# ALU.net
KiCad netlist of a schematic drawn in Altium Designer
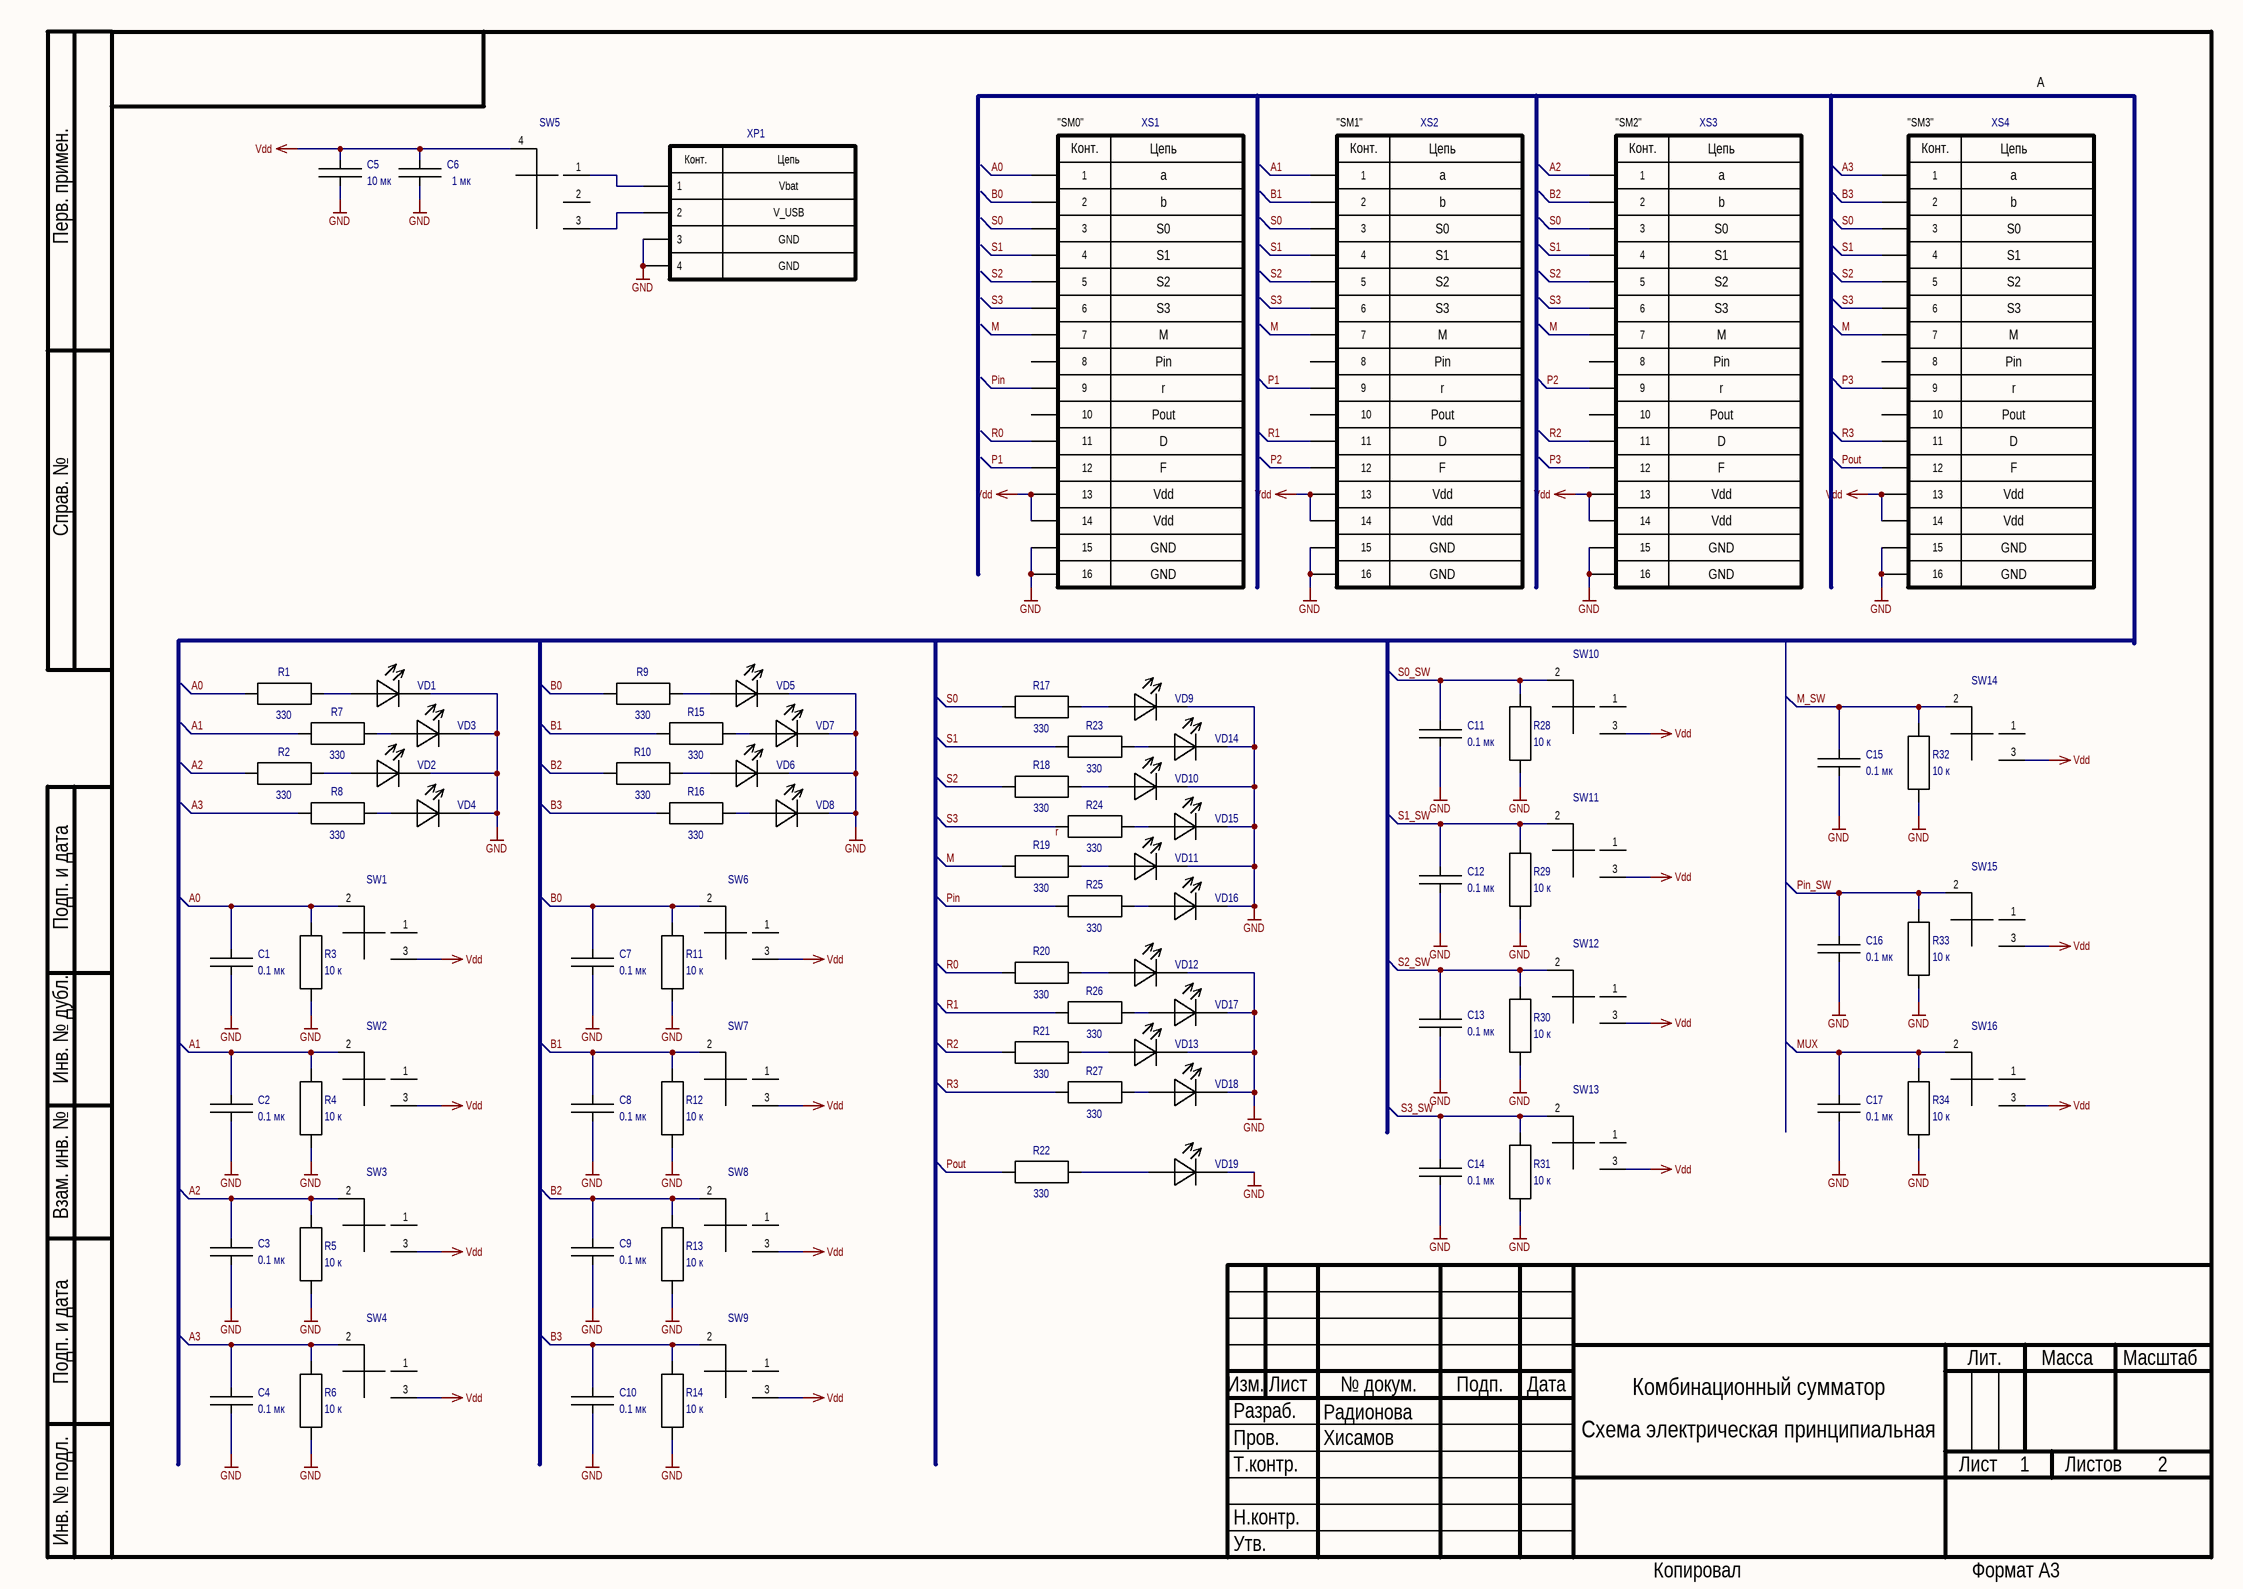
[diagram p0: ALU (4).SchDoc]

(export (version "E")
  (design (tool "Eeschema 10.0.6"))
  (components
    (comp (ref "C1")
      (value "0.1 мк")
      (footprint "platforma:C0603")
      (fields (field (name "Comment") "0.1 мкФ ±* * * *, *"))
      (libsource (lib "Lisaveta") (part "C"))
    )
    (comp (ref "C2")
      (value "0.1 мк")
      (footprint "platforma:C0603")
      (fields (field (name "Comment") "0.1 мкФ ±* * * *, *"))
      (libsource (lib "Lisaveta") (part "C"))
    )
    (comp (ref "C3")
      (value "0.1 мк")
      (footprint "platforma:C0603")
      (fields (field (name "Comment") "0.1 мкФ ±* * * *, *"))
      (libsource (lib "Lisaveta") (part "C"))
    )
    (comp (ref "C4")
      (value "0.1 мк")
      (footprint "platforma:C0603")
      (fields (field (name "Comment") "0.1 мкФ ±* * * *, *"))
      (libsource (lib "Lisaveta") (part "C"))
    )
    (comp (ref "C5")
      (value "10 мк")
      (footprint "platforma:C0603")
      (fields (field (name "Comment") "10 мкФ ±* * * *, *"))
      (libsource (lib "Lisaveta") (part "C"))
    )
    (comp (ref "C6")
      (value "1 мк")
      (footprint "platforma:C0603")
      (fields (field (name "Comment") "1 мкФ ±* * * *, *"))
      (libsource (lib "Lisaveta") (part "C"))
    )
    (comp (ref "C7")
      (value "0.1 мк")
      (footprint "platforma:C0603")
      (fields (field (name "Comment") "0.1 мкФ ±* * * *, *"))
      (libsource (lib "Lisaveta") (part "C"))
    )
    (comp (ref "C8")
      (value "0.1 мк")
      (footprint "platforma:C0603")
      (fields (field (name "Comment") "0.1 мкФ ±* * * *, *"))
      (libsource (lib "Lisaveta") (part "C"))
    )
    (comp (ref "C9")
      (value "0.1 мк")
      (footprint "platforma:C0603")
      (fields (field (name "Comment") "0.1 мкФ ±* * * *, *"))
      (libsource (lib "Lisaveta") (part "C"))
    )
    (comp (ref "C10")
      (value "0.1 мк")
      (footprint "platforma:C0603")
      (fields (field (name "Comment") "0.1 мкФ ±* * * *, *"))
      (libsource (lib "Lisaveta") (part "C"))
    )
    (comp (ref "C11")
      (value "0.1 мк")
      (footprint "platforma:C0603")
      (fields (field (name "Comment") "0.1 мкФ ±* * * *, *"))
      (libsource (lib "Lisaveta") (part "C"))
    )
    (comp (ref "C12")
      (value "0.1 мк")
      (footprint "platforma:C0603")
      (fields (field (name "Comment") "0.1 мкФ ±* * * *, *"))
      (libsource (lib "Lisaveta") (part "C"))
    )
    (comp (ref "C13")
      (value "0.1 мк")
      (footprint "platforma:C0603")
      (fields (field (name "Comment") "0.1 мкФ ±* * * *, *"))
      (libsource (lib "Lisaveta") (part "C"))
    )
    (comp (ref "C14")
      (value "0.1 мк")
      (footprint "platforma:C0603")
      (fields (field (name "Comment") "0.1 мкФ ±* * * *, *"))
      (libsource (lib "Lisaveta") (part "C"))
    )
    (comp (ref "C15")
      (value "0.1 мк")
      (footprint "platforma:C0603")
      (fields (field (name "Comment") "0.1 мкФ ±* * * *, *"))
      (libsource (lib "Lisaveta") (part "C"))
    )
    (comp (ref "C16")
      (value "0.1 мк")
      (footprint "platforma:C0603")
      (fields (field (name "Comment") "0.1 мкФ ±* * * *, *"))
      (libsource (lib "Lisaveta") (part "C"))
    )
    (comp (ref "C17")
      (value "0.1 мк")
      (footprint "platforma:C0603")
      (fields (field (name "Comment") "0.1 мкФ ±* * * *, *"))
      (libsource (lib "Lisaveta") (part "C"))
    )
    (comp (ref "R1")
      (value "330")
      (footprint "ALU:P1-12-0.1(0603)")
      (fields (field (name "Comment") "330Ом ±* *, *"))
      (libsource (lib "ALU") (part "R - Резистор"))
    )
    (comp (ref "R2")
      (value "330")
      (footprint "ALU:P1-12-0.1(0603)")
      (fields (field (name "Comment") "330Ом ±* *, *"))
      (libsource (lib "ALU") (part "R - Резистор"))
    )
    (comp (ref "R3")
      (value "10 к")
      (footprint "P1-12-0.1(0603)")
      (fields (field (name "Comment") "10 кОм ±* *, *"))
      (libsource (lib "Lisaveta") (part "R_1"))
    )
    (comp (ref "R4")
      (value "10 к")
      (footprint "P1-12-0.1(0603)")
      (fields (field (name "Comment") "10 кОм ±* *, *"))
      (libsource (lib "Lisaveta") (part "R_1"))
    )
    (comp (ref "R5")
      (value "10 к")
      (footprint "P1-12-0.1(0603)")
      (fields (field (name "Comment") "10 кОм ±* *, *"))
      (libsource (lib "Lisaveta") (part "R_1"))
    )
    (comp (ref "R6")
      (value "10 к")
      (footprint "P1-12-0.1(0603)")
      (fields (field (name "Comment") "10 кОм ±* *, *"))
      (libsource (lib "Lisaveta") (part "R_1"))
    )
    (comp (ref "R7")
      (value "330")
      (footprint "ALU:P1-12-0.1(0603)")
      (fields (field (name "Comment") "330Ом ±* *, *"))
      (libsource (lib "ALU") (part "R - Резистор"))
    )
    (comp (ref "R8")
      (value "330")
      (footprint "ALU:P1-12-0.1(0603)")
      (fields (field (name "Comment") "330Ом ±* *, *"))
      (libsource (lib "ALU") (part "R - Резистор"))
    )
    (comp (ref "R9")
      (value "330")
      (footprint "ALU:P1-12-0.1(0603)")
      (fields (field (name "Comment") "330Ом ±* *, *"))
      (libsource (lib "ALU") (part "R - Резистор"))
    )
    (comp (ref "R10")
      (value "330")
      (footprint "ALU:P1-12-0.1(0603)")
      (fields (field (name "Comment") "330Ом ±* *, *"))
      (libsource (lib "ALU") (part "R - Резистор"))
    )
    (comp (ref "R11")
      (value "10 к")
      (footprint "P1-12-0.1(0603)")
      (fields (field (name "Comment") "10 кОм ±* *, *"))
      (libsource (lib "Lisaveta") (part "R_1"))
    )
    (comp (ref "R12")
      (value "10 к")
      (footprint "P1-12-0.1(0603)")
      (fields (field (name "Comment") "10 кОм ±* *, *"))
      (libsource (lib "Lisaveta") (part "R_1"))
    )
    (comp (ref "R13")
      (value "10 к")
      (footprint "P1-12-0.1(0603)")
      (fields (field (name "Comment") "10 кОм ±* *, *"))
      (libsource (lib "Lisaveta") (part "R_1"))
    )
    (comp (ref "R14")
      (value "10 к")
      (footprint "P1-12-0.1(0603)")
      (fields (field (name "Comment") "10 кОм ±* *, *"))
      (libsource (lib "Lisaveta") (part "R_1"))
    )
    (comp (ref "R15")
      (value "330")
      (footprint "ALU:P1-12-0.1(0603)")
      (fields (field (name "Comment") "330Ом ±* *, *"))
      (libsource (lib "ALU") (part "R - Резистор"))
    )
    (comp (ref "R16")
      (value "330")
      (footprint "ALU:P1-12-0.1(0603)")
      (fields (field (name "Comment") "330Ом ±* *, *"))
      (libsource (lib "ALU") (part "R - Резистор"))
    )
    (comp (ref "R17")
      (value "330")
      (footprint "ALU:P1-12-0.1(0603)")
      (fields (field (name "Comment") "330Ом ±* *, *"))
      (libsource (lib "ALU") (part "R - Резистор"))
    )
    (comp (ref "R18")
      (value "330")
      (footprint "ALU:P1-12-0.1(0603)")
      (fields (field (name "Comment") "330Ом ±* *, *"))
      (libsource (lib "ALU") (part "R - Резистор"))
    )
    (comp (ref "R19")
      (value "330")
      (footprint "ALU:P1-12-0.1(0603)")
      (fields (field (name "Comment") "330Ом ±* *, *"))
      (libsource (lib "ALU") (part "R - Резистор"))
    )
    (comp (ref "R20")
      (value "330")
      (footprint "ALU:P1-12-0.1(0603)")
      (fields (field (name "Comment") "330Ом ±* *, *"))
      (libsource (lib "ALU") (part "R - Резистор"))
    )
    (comp (ref "R21")
      (value "330")
      (footprint "ALU:P1-12-0.1(0603)")
      (fields (field (name "Comment") "330Ом ±* *, *"))
      (libsource (lib "ALU") (part "R - Резистор"))
    )
    (comp (ref "R22")
      (value "330")
      (footprint "ALU:P1-12-0.1(0603)")
      (fields (field (name "Comment") "330Ом ±* *, *"))
      (libsource (lib "ALU") (part "R - Резистор"))
    )
    (comp (ref "R23")
      (value "330")
      (footprint "ALU:P1-12-0.1(0603)")
      (fields (field (name "Comment") "330Ом ±* *, *"))
      (libsource (lib "ALU") (part "R - Резистор"))
    )
    (comp (ref "R24")
      (value "330")
      (footprint "ALU:P1-12-0.1(0603)")
      (fields (field (name "Comment") "330Ом ±* *, *"))
      (libsource (lib "ALU") (part "R - Резистор"))
    )
    (comp (ref "R25")
      (value "330")
      (footprint "ALU:P1-12-0.1(0603)")
      (fields (field (name "Comment") "330Ом ±* *, *"))
      (libsource (lib "ALU") (part "R - Резистор"))
    )
    (comp (ref "R26")
      (value "330")
      (footprint "ALU:P1-12-0.1(0603)")
      (fields (field (name "Comment") "330Ом ±* *, *"))
      (libsource (lib "ALU") (part "R - Резистор"))
    )
    (comp (ref "R27")
      (value "330")
      (footprint "ALU:P1-12-0.1(0603)")
      (fields (field (name "Comment") "330Ом ±* *, *"))
      (libsource (lib "ALU") (part "R - Резистор"))
    )
    (comp (ref "R28")
      (value "10 к")
      (footprint "P1-12-0.1(0603)")
      (fields (field (name "Comment") "10 кОм ±* *, *"))
      (libsource (lib "Lisaveta") (part "R_1"))
    )
    (comp (ref "R29")
      (value "10 к")
      (footprint "P1-12-0.1(0603)")
      (fields (field (name "Comment") "10 кОм ±* *, *"))
      (libsource (lib "Lisaveta") (part "R_1"))
    )
    (comp (ref "R30")
      (value "10 к")
      (footprint "P1-12-0.1(0603)")
      (fields (field (name "Comment") "10 кОм ±* *, *"))
      (libsource (lib "Lisaveta") (part "R_1"))
    )
    (comp (ref "R31")
      (value "10 к")
      (footprint "P1-12-0.1(0603)")
      (fields (field (name "Comment") "10 кОм ±* *, *"))
      (libsource (lib "Lisaveta") (part "R_1"))
    )
    (comp (ref "R32")
      (value "10 к")
      (footprint "P1-12-0.1(0603)")
      (fields (field (name "Comment") "10 кОм ±* *, *"))
      (libsource (lib "Lisaveta") (part "R_1"))
    )
    (comp (ref "R33")
      (value "10 к")
      (footprint "P1-12-0.1(0603)")
      (fields (field (name "Comment") "10 кОм ±* *, *"))
      (libsource (lib "Lisaveta") (part "R_1"))
    )
    (comp (ref "R34")
      (value "10 к")
      (footprint "P1-12-0.1(0603)")
      (fields (field (name "Comment") "10 кОм ±* *, *"))
      (libsource (lib "Lisaveta") (part "R_1"))
    )
    (comp (ref "SW1")
      (value "SW_two")
      (footprint "platforma:MSS-22D18 MSS22D18G2")
      (libsource (lib "Lisaveta") (part "SW_two"))
    )
    (comp (ref "SW2")
      (value "SW_two")
      (footprint "platforma:MSS-22D18 MSS22D18G2")
      (libsource (lib "Lisaveta") (part "SW_two"))
    )
    (comp (ref "SW3")
      (value "SW_two")
      (footprint "platforma:MSS-22D18 MSS22D18G2")
      (libsource (lib "Lisaveta") (part "SW_two"))
    )
    (comp (ref "SW4")
      (value "SW_two")
      (footprint "platforma:MSS-22D18 MSS22D18G2")
      (libsource (lib "Lisaveta") (part "SW_two"))
    )
    (comp (ref "SW5") (value "*") (footprint "sw-3") (libsource (lib "*") (part "SW_three")))
    (comp (ref "SW6")
      (value "SW_two")
      (footprint "platforma:MSS-22D18 MSS22D18G2")
      (libsource (lib "Lisaveta") (part "SW_two"))
    )
    (comp (ref "SW7")
      (value "SW_two")
      (footprint "platforma:MSS-22D18 MSS22D18G2")
      (libsource (lib "Lisaveta") (part "SW_two"))
    )
    (comp (ref "SW8")
      (value "SW_two")
      (footprint "platforma:MSS-22D18 MSS22D18G2")
      (libsource (lib "Lisaveta") (part "SW_two"))
    )
    (comp (ref "SW9")
      (value "SW_two")
      (footprint "platforma:MSS-22D18 MSS22D18G2")
      (libsource (lib "Lisaveta") (part "SW_two"))
    )
    (comp (ref "SW10")
      (value "SW_two")
      (footprint "platforma:MSS-22D18 MSS22D18G2")
      (libsource (lib "Lisaveta") (part "SW_two"))
    )
    (comp (ref "SW11")
      (value "SW_two")
      (footprint "platforma:MSS-22D18 MSS22D18G2")
      (libsource (lib "Lisaveta") (part "SW_two"))
    )
    (comp (ref "SW12")
      (value "SW_two")
      (footprint "platforma:MSS-22D18 MSS22D18G2")
      (libsource (lib "Lisaveta") (part "SW_two"))
    )
    (comp (ref "SW13")
      (value "SW_two")
      (footprint "platforma:MSS-22D18 MSS22D18G2")
      (libsource (lib "Lisaveta") (part "SW_two"))
    )
    (comp (ref "SW14")
      (value "SW_two")
      (footprint "platforma:MSS-22D18 MSS22D18G2")
      (libsource (lib "Lisaveta") (part "SW_two"))
    )
    (comp (ref "SW15")
      (value "SW_two")
      (footprint "platforma:MSS-22D18 MSS22D18G2")
      (libsource (lib "Lisaveta") (part "SW_two"))
    )
    (comp (ref "SW16")
      (value "SW_two")
      (footprint "platforma:MSS-22D18 MSS22D18G2")
      (libsource (lib "") (part "SW_two_1"))
    )
    (comp (ref "VD1")
      (value "VD - Светодиод")
      (footprint "ALU:LED 0603")
      (libsource (lib "ALU") (part "VD - Светодиод"))
    )
    (comp (ref "VD2")
      (value "VD - Светодиод")
      (footprint "ALU:LED 0603")
      (libsource (lib "ALU") (part "VD - Светодиод"))
    )
    (comp (ref "VD3")
      (value "VD - Светодиод")
      (footprint "ALU:LED 0603")
      (libsource (lib "ALU") (part "VD - Светодиод"))
    )
    (comp (ref "VD4")
      (value "VD - Светодиод")
      (footprint "ALU:LED 0603")
      (libsource (lib "ALU") (part "VD - Светодиод"))
    )
    (comp (ref "VD5")
      (value "VD - Светодиод")
      (footprint "ALU:LED 0603")
      (libsource (lib "ALU") (part "VD - Светодиод"))
    )
    (comp (ref "VD6")
      (value "VD - Светодиод")
      (footprint "ALU:LED 0603")
      (libsource (lib "ALU") (part "VD - Светодиод"))
    )
    (comp (ref "VD7")
      (value "VD - Светодиод")
      (footprint "ALU:LED 0603")
      (libsource (lib "ALU") (part "VD - Светодиод"))
    )
    (comp (ref "VD8")
      (value "VD - Светодиод")
      (footprint "ALU:LED 0603")
      (libsource (lib "ALU") (part "VD - Светодиод"))
    )
    (comp (ref "VD9")
      (value "VD - Светодиод")
      (footprint "ALU:LED 0603")
      (libsource (lib "ALU") (part "VD - Светодиод"))
    )
    (comp (ref "VD10")
      (value "VD - Светодиод")
      (footprint "ALU:LED 0603")
      (libsource (lib "ALU") (part "VD - Светодиод"))
    )
    (comp (ref "VD11")
      (value "VD - Светодиод")
      (footprint "ALU:LED 0603")
      (libsource (lib "ALU") (part "VD - Светодиод"))
    )
    (comp (ref "VD12")
      (value "VD - Светодиод")
      (footprint "ALU:LED 0603")
      (libsource (lib "ALU") (part "VD - Светодиод"))
    )
    (comp (ref "VD13")
      (value "VD - Светодиод")
      (footprint "ALU:LED 0603")
      (libsource (lib "ALU") (part "VD - Светодиод"))
    )
    (comp (ref "VD14")
      (value "VD - Светодиод")
      (footprint "ALU:LED 0603")
      (libsource (lib "ALU") (part "VD - Светодиод"))
    )
    (comp (ref "VD15")
      (value "VD - Светодиод")
      (footprint "ALU:LED 0603")
      (libsource (lib "ALU") (part "VD - Светодиод"))
    )
    (comp (ref "VD16")
      (value "VD - Светодиод")
      (footprint "ALU:LED 0603")
      (libsource (lib "ALU") (part "VD - Светодиод"))
    )
    (comp (ref "VD17")
      (value "VD - Светодиод")
      (footprint "ALU:LED 0603")
      (libsource (lib "ALU") (part "VD - Светодиод"))
    )
    (comp (ref "VD18")
      (value "VD - Светодиод")
      (footprint "ALU:LED 0603")
      (libsource (lib "ALU") (part "VD - Светодиод"))
    )
    (comp (ref "VD19")
      (value "VD - Светодиод")
      (footprint "ALU:LED 0603")
      (libsource (lib "ALU") (part "VD - Светодиод"))
    )
    (comp (ref "XP1")
      (value "XP - Вилка - х4")
      (fields
        (field (name "1") "Vbat")
        (field (name "2") "V_USB")
        (field (name "3") "GND")
        (field (name "4") "GND")
      )
      (libsource (lib "*") (part "XP - Вилка - х4"))
    )
    (comp (ref "XS1")
      (value "XS - Розетка - PBD-16")
      (footprint "ALU:PLD-16Norm")
      (libsource (lib "ALU") (part "XS -PBD-16"))
    )
    (comp (ref "XS2")
      (value "XS - Розетка - PBD-16")
      (footprint "ALU:PLD-16Norm")
      (libsource (lib "ALU") (part "XS -PBD-16"))
    )
    (comp (ref "XS3")
      (value "XS - Розетка - PBD-16")
      (footprint "ALU:PLD-16Norm")
      (libsource (lib "ALU") (part "XS -PBD-16"))
    )
    (comp (ref "XS4")
      (value "XS - Розетка - PBD-16")
      (footprint "ALU:PLD-16Norm")
      (libsource (lib "ALU") (part "XS -PBD-16"))
    )
  )
  (nets
    (net (code "1") (name "/A0") (class "Default")
      (node (ref "C1") (pin "2") (pinfunction "2_2") (pintype "passive"))
      (node (ref "R1") (pin "1") (pinfunction "1_1") (pintype "passive"))
      (node (ref "R3") (pin "1") (pinfunction "1_1") (pintype "passive"))
      (node (ref "SW1") (pin "2") (pinfunction "2_2") (pintype "passive"))
      (node (ref "XS1") (pin "1") (pinfunction "1_1") (pintype "passive"))
    )
    (net (code "2") (name "/A1") (class "Default")
      (node (ref "C2") (pin "2") (pinfunction "2_2") (pintype "passive"))
      (node (ref "R4") (pin "1") (pinfunction "1_1") (pintype "passive"))
      (node (ref "R7") (pin "1") (pinfunction "1_1") (pintype "passive"))
      (node (ref "SW2") (pin "2") (pinfunction "2_2") (pintype "passive"))
      (node (ref "XS2") (pin "1") (pinfunction "1_1") (pintype "passive"))
    )
    (net (code "3") (name "/A2") (class "Default")
      (node (ref "C3") (pin "2") (pinfunction "2_2") (pintype "passive"))
      (node (ref "R2") (pin "1") (pinfunction "1_1") (pintype "passive"))
      (node (ref "R5") (pin "1") (pinfunction "1_1") (pintype "passive"))
      (node (ref "SW3") (pin "2") (pinfunction "2_2") (pintype "passive"))
      (node (ref "XS3") (pin "1") (pinfunction "1_1") (pintype "passive"))
    )
    (net (code "4") (name "/A3") (class "Default")
      (node (ref "C4") (pin "2") (pinfunction "2_2") (pintype "passive"))
      (node (ref "R6") (pin "1") (pinfunction "1_1") (pintype "passive"))
      (node (ref "R8") (pin "1") (pinfunction "1_1") (pintype "passive"))
      (node (ref "SW4") (pin "2") (pinfunction "2_2") (pintype "passive"))
      (node (ref "XS4") (pin "1") (pinfunction "1_1") (pintype "passive"))
    )
    (net (code "5") (name "/B0") (class "Default")
      (node (ref "C7") (pin "2") (pinfunction "2_2") (pintype "passive"))
      (node (ref "R11") (pin "1") (pinfunction "1_1") (pintype "passive"))
      (node (ref "R9") (pin "1") (pinfunction "1_1") (pintype "passive"))
      (node (ref "SW6") (pin "2") (pinfunction "2_2") (pintype "passive"))
      (node (ref "XS1") (pin "2") (pinfunction "2_2") (pintype "passive"))
    )
    (net (code "6") (name "/B1") (class "Default")
      (node (ref "C8") (pin "2") (pinfunction "2_2") (pintype "passive"))
      (node (ref "R12") (pin "1") (pinfunction "1_1") (pintype "passive"))
      (node (ref "R15") (pin "1") (pinfunction "1_1") (pintype "passive"))
      (node (ref "SW7") (pin "2") (pinfunction "2_2") (pintype "passive"))
      (node (ref "XS2") (pin "2") (pinfunction "2_2") (pintype "passive"))
    )
    (net (code "7") (name "/B2") (class "Default")
      (node (ref "C9") (pin "2") (pinfunction "2_2") (pintype "passive"))
      (node (ref "R10") (pin "1") (pinfunction "1_1") (pintype "passive"))
      (node (ref "R13") (pin "1") (pinfunction "1_1") (pintype "passive"))
      (node (ref "SW8") (pin "2") (pinfunction "2_2") (pintype "passive"))
      (node (ref "XS3") (pin "2") (pinfunction "2_2") (pintype "passive"))
    )
    (net (code "8") (name "/B3") (class "Default")
      (node (ref "C10") (pin "2") (pinfunction "2_2") (pintype "passive"))
      (node (ref "R14") (pin "1") (pinfunction "1_1") (pintype "passive"))
      (node (ref "R16") (pin "1") (pinfunction "1_1") (pintype "passive"))
      (node (ref "SW9") (pin "2") (pinfunction "2_2") (pintype "passive"))
      (node (ref "XS4") (pin "2") (pinfunction "2_2") (pintype "passive"))
    )
    (net (code "9") (name "/M") (class "Default")
      (node (ref "R19") (pin "1") (pinfunction "1_1") (pintype "passive"))
      (node (ref "XS1") (pin "7") (pinfunction "7_7") (pintype "passive"))
      (node (ref "XS2") (pin "7") (pinfunction "7_7") (pintype "passive"))
      (node (ref "XS3") (pin "7") (pinfunction "7_7") (pintype "passive"))
      (node (ref "XS4") (pin "7") (pinfunction "7_7") (pintype "passive"))
    )
    (net (code "10") (name "/MUX") (class "Default")
      (node (ref "C17") (pin "2") (pinfunction "2_2") (pintype "passive"))
      (node (ref "R34") (pin "1") (pinfunction "1_1") (pintype "passive"))
      (node (ref "SW16") (pin "2") (pinfunction "2_2") (pintype "passive"))
    )
    (net (code "11") (name "/M_SW") (class "Default")
      (node (ref "C15") (pin "2") (pinfunction "2_2") (pintype "passive"))
      (node (ref "R32") (pin "1") (pinfunction "1_1") (pintype "passive"))
      (node (ref "SW14") (pin "2") (pinfunction "2_2") (pintype "passive"))
    )
    (net (code "12") (name "/P1") (class "Default")
      (node (ref "XS1") (pin "12") (pinfunction "12_12") (pintype "passive"))
      (node (ref "XS2") (pin "9") (pinfunction "9_9") (pintype "passive"))
    )
    (net (code "13") (name "/P2") (class "Default")
      (node (ref "XS2") (pin "12") (pinfunction "12_12") (pintype "passive"))
      (node (ref "XS3") (pin "9") (pinfunction "9_9") (pintype "passive"))
    )
    (net (code "14") (name "/P3") (class "Default")
      (node (ref "XS3") (pin "12") (pinfunction "12_12") (pintype "passive"))
      (node (ref "XS4") (pin "9") (pinfunction "9_9") (pintype "passive"))
    )
    (net (code "15") (name "/Pin") (class "Default")
      (node (ref "R25") (pin "1") (pinfunction "1_1") (pintype "passive"))
      (node (ref "XS1") (pin "9") (pinfunction "9_9") (pintype "passive"))
    )
    (net (code "16") (name "/Pin_SW") (class "Default")
      (node (ref "C16") (pin "2") (pinfunction "2_2") (pintype "passive"))
      (node (ref "R33") (pin "1") (pinfunction "1_1") (pintype "passive"))
      (node (ref "SW15") (pin "2") (pinfunction "2_2") (pintype "passive"))
    )
    (net (code "17") (name "/Pout") (class "Default")
      (node (ref "R22") (pin "1") (pinfunction "1_1") (pintype "passive"))
      (node (ref "XS4") (pin "12") (pinfunction "12_12") (pintype "passive"))
    )
    (net (code "18") (name "/R0") (class "Default")
      (node (ref "R20") (pin "1") (pinfunction "1_1") (pintype "passive"))
      (node (ref "XS1") (pin "11") (pinfunction "11_11") (pintype "passive"))
    )
    (net (code "19") (name "/R1") (class "Default")
      (node (ref "R26") (pin "1") (pinfunction "1_1") (pintype "passive"))
      (node (ref "XS2") (pin "11") (pinfunction "11_11") (pintype "passive"))
    )
    (net (code "20") (name "/R2") (class "Default")
      (node (ref "R21") (pin "1") (pinfunction "1_1") (pintype "passive"))
      (node (ref "XS3") (pin "11") (pinfunction "11_11") (pintype "passive"))
    )
    (net (code "21") (name "/R3") (class "Default")
      (node (ref "R27") (pin "1") (pinfunction "1_1") (pintype "passive"))
      (node (ref "XS4") (pin "11") (pinfunction "11_11") (pintype "passive"))
    )
    (net (code "22") (name "/S0") (class "Default")
      (node (ref "R17") (pin "1") (pinfunction "1_1") (pintype "passive"))
      (node (ref "XS1") (pin "3") (pinfunction "3_3") (pintype "passive"))
      (node (ref "XS2") (pin "3") (pinfunction "3_3") (pintype "passive"))
      (node (ref "XS3") (pin "3") (pinfunction "3_3") (pintype "passive"))
      (node (ref "XS4") (pin "3") (pinfunction "3_3") (pintype "passive"))
    )
    (net (code "23") (name "/S0_SW") (class "Default")
      (node (ref "C11") (pin "2") (pinfunction "2_2") (pintype "passive"))
      (node (ref "R28") (pin "1") (pinfunction "1_1") (pintype "passive"))
      (node (ref "SW10") (pin "2") (pinfunction "2_2") (pintype "passive"))
    )
    (net (code "24") (name "/S1") (class "Default")
      (node (ref "R23") (pin "1") (pinfunction "1_1") (pintype "passive"))
      (node (ref "XS1") (pin "4") (pinfunction "4_4") (pintype "passive"))
      (node (ref "XS2") (pin "4") (pinfunction "4_4") (pintype "passive"))
      (node (ref "XS3") (pin "4") (pinfunction "4_4") (pintype "passive"))
      (node (ref "XS4") (pin "4") (pinfunction "4_4") (pintype "passive"))
    )
    (net (code "25") (name "/S1_SW") (class "Default")
      (node (ref "C12") (pin "2") (pinfunction "2_2") (pintype "passive"))
      (node (ref "R29") (pin "1") (pinfunction "1_1") (pintype "passive"))
      (node (ref "SW11") (pin "2") (pinfunction "2_2") (pintype "passive"))
    )
    (net (code "26") (name "/S2") (class "Default")
      (node (ref "R18") (pin "1") (pinfunction "1_1") (pintype "passive"))
      (node (ref "XS1") (pin "5") (pinfunction "5_5") (pintype "passive"))
      (node (ref "XS2") (pin "5") (pinfunction "5_5") (pintype "passive"))
      (node (ref "XS3") (pin "5") (pinfunction "5_5") (pintype "passive"))
      (node (ref "XS4") (pin "5") (pinfunction "5_5") (pintype "passive"))
    )
    (net (code "27") (name "/S2_SW") (class "Default")
      (node (ref "C13") (pin "2") (pinfunction "2_2") (pintype "passive"))
      (node (ref "R30") (pin "1") (pinfunction "1_1") (pintype "passive"))
      (node (ref "SW12") (pin "2") (pinfunction "2_2") (pintype "passive"))
    )
    (net (code "28") (name "/S3") (class "Default")
      (node (ref "R24") (pin "1") (pinfunction "1_1") (pintype "passive"))
      (node (ref "XS1") (pin "6") (pinfunction "6_6") (pintype "passive"))
      (node (ref "XS2") (pin "6") (pinfunction "6_6") (pintype "passive"))
      (node (ref "XS3") (pin "6") (pinfunction "6_6") (pintype "passive"))
      (node (ref "XS4") (pin "6") (pinfunction "6_6") (pintype "passive"))
    )
    (net (code "29") (name "/S3_SW") (class "Default")
      (node (ref "C14") (pin "2") (pinfunction "2_2") (pintype "passive"))
      (node (ref "R31") (pin "1") (pinfunction "1_1") (pintype "passive"))
      (node (ref "SW13") (pin "2") (pinfunction "2_2") (pintype "passive"))
    )
    (net (code "31") (name "GND") (class "Default")
      (node (ref "C1") (pin "1") (pinfunction "1_1") (pintype "passive"))
      (node (ref "C10") (pin "1") (pinfunction "1_1") (pintype "passive"))
      (node (ref "C11") (pin "1") (pinfunction "1_1") (pintype "passive"))
      (node (ref "C12") (pin "1") (pinfunction "1_1") (pintype "passive"))
      (node (ref "C13") (pin "1") (pinfunction "1_1") (pintype "passive"))
      (node (ref "C14") (pin "1") (pinfunction "1_1") (pintype "passive"))
      (node (ref "C15") (pin "1") (pinfunction "1_1") (pintype "passive"))
      (node (ref "C16") (pin "1") (pinfunction "1_1") (pintype "passive"))
      (node (ref "C17") (pin "1") (pinfunction "1_1") (pintype "passive"))
      (node (ref "C2") (pin "1") (pinfunction "1_1") (pintype "passive"))
      (node (ref "C3") (pin "1") (pinfunction "1_1") (pintype "passive"))
      (node (ref "C4") (pin "1") (pinfunction "1_1") (pintype "passive"))
      (node (ref "C5") (pin "1") (pinfunction "1_1") (pintype "passive"))
      (node (ref "C6") (pin "1") (pinfunction "1_1") (pintype "passive"))
      (node (ref "C7") (pin "1") (pinfunction "1_1") (pintype "passive"))
      (node (ref "C8") (pin "1") (pinfunction "1_1") (pintype "passive"))
      (node (ref "C9") (pin "1") (pinfunction "1_1") (pintype "passive"))
      (node (ref "R11") (pin "2") (pinfunction "2_2") (pintype "passive"))
      (node (ref "R12") (pin "2") (pinfunction "2_2") (pintype "passive"))
      (node (ref "R13") (pin "2") (pinfunction "2_2") (pintype "passive"))
      (node (ref "R14") (pin "2") (pinfunction "2_2") (pintype "passive"))
      (node (ref "R28") (pin "2") (pinfunction "2_2") (pintype "passive"))
      (node (ref "R29") (pin "2") (pinfunction "2_2") (pintype "passive"))
      (node (ref "R3") (pin "2") (pinfunction "2_2") (pintype "passive"))
      (node (ref "R30") (pin "2") (pinfunction "2_2") (pintype "passive"))
      (node (ref "R31") (pin "2") (pinfunction "2_2") (pintype "passive"))
      (node (ref "R32") (pin "2") (pinfunction "2_2") (pintype "passive"))
      (node (ref "R33") (pin "2") (pinfunction "2_2") (pintype "passive"))
      (node (ref "R34") (pin "2") (pinfunction "2_2") (pintype "passive"))
      (node (ref "R4") (pin "2") (pinfunction "2_2") (pintype "passive"))
      (node (ref "R5") (pin "2") (pinfunction "2_2") (pintype "passive"))
      (node (ref "R6") (pin "2") (pinfunction "2_2") (pintype "passive"))
      (node (ref "VD1") (pin "2") (pinfunction "C_2") (pintype "passive"))
      (node (ref "VD10") (pin "2") (pinfunction "C_2") (pintype "passive"))
      (node (ref "VD11") (pin "2") (pinfunction "C_2") (pintype "passive"))
      (node (ref "VD12") (pin "2") (pinfunction "C_2") (pintype "passive"))
      (node (ref "VD13") (pin "2") (pinfunction "C_2") (pintype "passive"))
      (node (ref "VD14") (pin "2") (pinfunction "C_2") (pintype "passive"))
      (node (ref "VD15") (pin "2") (pinfunction "C_2") (pintype "passive"))
      (node (ref "VD16") (pin "2") (pinfunction "C_2") (pintype "passive"))
      (node (ref "VD17") (pin "2") (pinfunction "C_2") (pintype "passive"))
      (node (ref "VD18") (pin "2") (pinfunction "C_2") (pintype "passive"))
      (node (ref "VD19") (pin "2") (pinfunction "C_2") (pintype "passive"))
      (node (ref "VD2") (pin "2") (pinfunction "C_2") (pintype "passive"))
      (node (ref "VD3") (pin "2") (pinfunction "C_2") (pintype "passive"))
      (node (ref "VD4") (pin "2") (pinfunction "C_2") (pintype "passive"))
      (node (ref "VD5") (pin "2") (pinfunction "C_2") (pintype "passive"))
      (node (ref "VD6") (pin "2") (pinfunction "C_2") (pintype "passive"))
      (node (ref "VD7") (pin "2") (pinfunction "C_2") (pintype "passive"))
      (node (ref "VD8") (pin "2") (pinfunction "C_2") (pintype "passive"))
      (node (ref "VD9") (pin "2") (pinfunction "C_2") (pintype "passive"))
      (node (ref "XP1") (pin "3") (pinfunction "3_3") (pintype "passive"))
      (node (ref "XP1") (pin "4") (pinfunction "4_4") (pintype "passive"))
      (node (ref "XS1") (pin "15") (pinfunction "15_15") (pintype "passive"))
      (node (ref "XS1") (pin "16") (pinfunction "16_16") (pintype "passive"))
      (node (ref "XS2") (pin "15") (pinfunction "15_15") (pintype "passive"))
      (node (ref "XS2") (pin "16") (pinfunction "16_16") (pintype "passive"))
      (node (ref "XS3") (pin "15") (pinfunction "15_15") (pintype "passive"))
      (node (ref "XS3") (pin "16") (pinfunction "16_16") (pintype "passive"))
      (node (ref "XS4") (pin "15") (pinfunction "15_15") (pintype "passive"))
      (node (ref "XS4") (pin "16") (pinfunction "16_16") (pintype "passive"))
    )
    (net (code "32") (name "Net-(SW5-Pad1)") (class "Default")
      (node (ref "SW5") (pin "1") (pinfunction "1_1") (pintype "passive"))
      (node (ref "XP1") (pin "1") (pinfunction "1_1") (pintype "passive"))
    )
    (net (code "33") (name "Net-(SW5-Pad3)") (class "Default")
      (node (ref "SW5") (pin "3") (pinfunction "3_3") (pintype "passive"))
      (node (ref "XP1") (pin "2") (pinfunction "2_2") (pintype "passive"))
    )
    (net (code "34") (name "Net-(VD1-A)") (class "Default")
      (node (ref "R1") (pin "2") (pinfunction "2_2") (pintype "passive"))
      (node (ref "VD1") (pin "1") (pinfunction "A_1") (pintype "passive"))
    )
    (net (code "35") (name "Net-(VD2-A)") (class "Default")
      (node (ref "R2") (pin "2") (pinfunction "2_2") (pintype "passive"))
      (node (ref "VD2") (pin "1") (pinfunction "A_1") (pintype "passive"))
    )
    (net (code "36") (name "Net-(VD3-A)") (class "Default")
      (node (ref "R7") (pin "2") (pinfunction "2_2") (pintype "passive"))
      (node (ref "VD3") (pin "1") (pinfunction "A_1") (pintype "passive"))
    )
    (net (code "37") (name "Net-(VD4-A)") (class "Default")
      (node (ref "R8") (pin "2") (pinfunction "2_2") (pintype "passive"))
      (node (ref "VD4") (pin "1") (pinfunction "A_1") (pintype "passive"))
    )
    (net (code "38") (name "Net-(VD5-A)") (class "Default")
      (node (ref "R9") (pin "2") (pinfunction "2_2") (pintype "passive"))
      (node (ref "VD5") (pin "1") (pinfunction "A_1") (pintype "passive"))
    )
    (net (code "39") (name "Net-(VD6-A)") (class "Default")
      (node (ref "R10") (pin "2") (pinfunction "2_2") (pintype "passive"))
      (node (ref "VD6") (pin "1") (pinfunction "A_1") (pintype "passive"))
    )
    (net (code "40") (name "Net-(VD7-A)") (class "Default")
      (node (ref "R15") (pin "2") (pinfunction "2_2") (pintype "passive"))
      (node (ref "VD7") (pin "1") (pinfunction "A_1") (pintype "passive"))
    )
    (net (code "41") (name "Net-(VD8-A)") (class "Default")
      (node (ref "R16") (pin "2") (pinfunction "2_2") (pintype "passive"))
      (node (ref "VD8") (pin "1") (pinfunction "A_1") (pintype "passive"))
    )
    (net (code "42") (name "Net-(VD9-A)") (class "Default")
      (node (ref "R17") (pin "2") (pinfunction "2_2") (pintype "passive"))
      (node (ref "VD9") (pin "1") (pinfunction "A_1") (pintype "passive"))
    )
    (net (code "43") (name "Net-(VD10-A)") (class "Default")
      (node (ref "R18") (pin "2") (pinfunction "2_2") (pintype "passive"))
      (node (ref "VD10") (pin "1") (pinfunction "A_1") (pintype "passive"))
    )
    (net (code "44") (name "Net-(VD11-A)") (class "Default")
      (node (ref "R19") (pin "2") (pinfunction "2_2") (pintype "passive"))
      (node (ref "VD11") (pin "1") (pinfunction "A_1") (pintype "passive"))
    )
    (net (code "45") (name "Net-(VD12-A)") (class "Default")
      (node (ref "R20") (pin "2") (pinfunction "2_2") (pintype "passive"))
      (node (ref "VD12") (pin "1") (pinfunction "A_1") (pintype "passive"))
    )
    (net (code "46") (name "Net-(VD13-A)") (class "Default")
      (node (ref "R21") (pin "2") (pinfunction "2_2") (pintype "passive"))
      (node (ref "VD13") (pin "1") (pinfunction "A_1") (pintype "passive"))
    )
    (net (code "47") (name "Net-(VD14-A)") (class "Default")
      (node (ref "R23") (pin "2") (pinfunction "2_2") (pintype "passive"))
      (node (ref "VD14") (pin "1") (pinfunction "A_1") (pintype "passive"))
    )
    (net (code "48") (name "Net-(VD15-A)") (class "Default")
      (node (ref "R24") (pin "2") (pinfunction "2_2") (pintype "passive"))
      (node (ref "VD15") (pin "1") (pinfunction "A_1") (pintype "passive"))
    )
    (net (code "49") (name "Net-(VD16-A)") (class "Default")
      (node (ref "R25") (pin "2") (pinfunction "2_2") (pintype "passive"))
      (node (ref "VD16") (pin "1") (pinfunction "A_1") (pintype "passive"))
    )
    (net (code "50") (name "Net-(VD17-A)") (class "Default")
      (node (ref "R26") (pin "2") (pinfunction "2_2") (pintype "passive"))
      (node (ref "VD17") (pin "1") (pinfunction "A_1") (pintype "passive"))
    )
    (net (code "51") (name "Net-(VD18-A)") (class "Default")
      (node (ref "R27") (pin "2") (pinfunction "2_2") (pintype "passive"))
      (node (ref "VD18") (pin "1") (pinfunction "A_1") (pintype "passive"))
    )
    (net (code "52") (name "Net-(VD19-A)") (class "Default")
      (node (ref "R22") (pin "2") (pinfunction "2_2") (pintype "passive"))
      (node (ref "VD19") (pin "1") (pinfunction "A_1") (pintype "passive"))
    )
    (net (code "53") (name "Vdd") (class "Default")
      (node (ref "C5") (pin "2") (pinfunction "2_2") (pintype "passive"))
      (node (ref "C6") (pin "2") (pinfunction "2_2") (pintype "passive"))
      (node (ref "SW1") (pin "3") (pinfunction "3_3") (pintype "passive"))
      (node (ref "SW10") (pin "3") (pinfunction "3_3") (pintype "passive"))
      (node (ref "SW11") (pin "3") (pinfunction "3_3") (pintype "passive"))
      (node (ref "SW12") (pin "3") (pinfunction "3_3") (pintype "passive"))
      (node (ref "SW13") (pin "3") (pinfunction "3_3") (pintype "passive"))
      (node (ref "SW14") (pin "3") (pinfunction "3_3") (pintype "passive"))
      (node (ref "SW15") (pin "3") (pinfunction "3_3") (pintype "passive"))
      (node (ref "SW16") (pin "3") (pinfunction "3_3") (pintype "passive"))
      (node (ref "SW2") (pin "3") (pinfunction "3_3") (pintype "passive"))
      (node (ref "SW3") (pin "3") (pinfunction "3_3") (pintype "passive"))
      (node (ref "SW4") (pin "3") (pinfunction "3_3") (pintype "passive"))
      (node (ref "SW5") (pin "4") (pinfunction "4_4") (pintype "passive"))
      (node (ref "SW6") (pin "3") (pinfunction "3_3") (pintype "passive"))
      (node (ref "SW7") (pin "3") (pinfunction "3_3") (pintype "passive"))
      (node (ref "SW8") (pin "3") (pinfunction "3_3") (pintype "passive"))
      (node (ref "SW9") (pin "3") (pinfunction "3_3") (pintype "passive"))
      (node (ref "XS1") (pin "13") (pinfunction "13_13") (pintype "passive"))
      (node (ref "XS1") (pin "14") (pinfunction "14_14") (pintype "passive"))
      (node (ref "XS2") (pin "13") (pinfunction "13_13") (pintype "passive"))
      (node (ref "XS2") (pin "14") (pinfunction "14_14") (pintype "passive"))
      (node (ref "XS3") (pin "13") (pinfunction "13_13") (pintype "passive"))
      (node (ref "XS3") (pin "14") (pinfunction "14_14") (pintype "passive"))
      (node (ref "XS4") (pin "13") (pinfunction "13_13") (pintype "passive"))
      (node (ref "XS4") (pin "14") (pinfunction "14_14") (pintype "passive"))
    )
    (net (code "54") (name "unconnected-(SW1-Pad1)") (class "Default")
      (node (ref "SW1") (pin "1") (pinfunction "1_1") (pintype "passive"))
    )
    (net (code "55") (name "unconnected-(SW2-Pad1)") (class "Default")
      (node (ref "SW2") (pin "1") (pinfunction "1_1") (pintype "passive"))
    )
    (net (code "56") (name "unconnected-(SW3-Pad1)") (class "Default")
      (node (ref "SW3") (pin "1") (pinfunction "1_1") (pintype "passive"))
    )
    (net (code "57") (name "unconnected-(SW4-Pad1)") (class "Default")
      (node (ref "SW4") (pin "1") (pinfunction "1_1") (pintype "passive"))
    )
    (net (code "58") (name "unconnected-(SW5-Pad2)") (class "Default")
      (node (ref "SW5") (pin "2") (pinfunction "2_2") (pintype "passive"))
    )
    (net (code "59") (name "unconnected-(SW6-Pad1)") (class "Default")
      (node (ref "SW6") (pin "1") (pinfunction "1_1") (pintype "passive"))
    )
    (net (code "60") (name "unconnected-(SW7-Pad1)") (class "Default")
      (node (ref "SW7") (pin "1") (pinfunction "1_1") (pintype "passive"))
    )
    (net (code "61") (name "unconnected-(SW8-Pad1)") (class "Default")
      (node (ref "SW8") (pin "1") (pinfunction "1_1") (pintype "passive"))
    )
    (net (code "62") (name "unconnected-(SW9-Pad1)") (class "Default")
      (node (ref "SW9") (pin "1") (pinfunction "1_1") (pintype "passive"))
    )
    (net (code "63") (name "unconnected-(SW10-Pad1)") (class "Default")
      (node (ref "SW10") (pin "1") (pinfunction "1_1") (pintype "passive"))
    )
    (net (code "64") (name "unconnected-(SW11-Pad1)") (class "Default")
      (node (ref "SW11") (pin "1") (pinfunction "1_1") (pintype "passive"))
    )
    (net (code "65") (name "unconnected-(SW12-Pad1)") (class "Default")
      (node (ref "SW12") (pin "1") (pinfunction "1_1") (pintype "passive"))
    )
    (net (code "66") (name "unconnected-(SW13-Pad1)") (class "Default")
      (node (ref "SW13") (pin "1") (pinfunction "1_1") (pintype "passive"))
    )
    (net (code "67") (name "unconnected-(SW14-Pad1)") (class "Default")
      (node (ref "SW14") (pin "1") (pinfunction "1_1") (pintype "passive"))
    )
    (net (code "68") (name "unconnected-(SW15-Pad1)") (class "Default")
      (node (ref "SW15") (pin "1") (pinfunction "1_1") (pintype "passive"))
    )
    (net (code "69") (name "unconnected-(SW16-Pad1)") (class "Default")
      (node (ref "SW16") (pin "1") (pinfunction "1_1") (pintype "passive"))
    )
    (net (code "70") (name "unconnected-(XS1-Pad8)") (class "Default")
      (node (ref "XS1") (pin "8") (pinfunction "8_8") (pintype "passive"))
    )
    (net (code "71") (name "unconnected-(XS1-Pad10)") (class "Default")
      (node (ref "XS1") (pin "10") (pinfunction "10_10") (pintype "passive"))
    )
    (net (code "72") (name "unconnected-(XS2-Pad8)") (class "Default")
      (node (ref "XS2") (pin "8") (pinfunction "8_8") (pintype "passive"))
    )
    (net (code "73") (name "unconnected-(XS2-Pad10)") (class "Default")
      (node (ref "XS2") (pin "10") (pinfunction "10_10") (pintype "passive"))
    )
    (net (code "74") (name "unconnected-(XS3-Pad8)") (class "Default")
      (node (ref "XS3") (pin "8") (pinfunction "8_8") (pintype "passive"))
    )
    (net (code "75") (name "unconnected-(XS3-Pad10)") (class "Default")
      (node (ref "XS3") (pin "10") (pinfunction "10_10") (pintype "passive"))
    )
    (net (code "76") (name "unconnected-(XS4-Pad8)") (class "Default")
      (node (ref "XS4") (pin "8") (pinfunction "8_8") (pintype "passive"))
    )
    (net (code "77") (name "unconnected-(XS4-Pad10)") (class "Default")
      (node (ref "XS4") (pin "10") (pinfunction "10_10") (pintype "passive"))
    )
  )
)
